# NanoRS485-MySens-v015.net
KiCad netlist of a schematic drawn in EAGLE
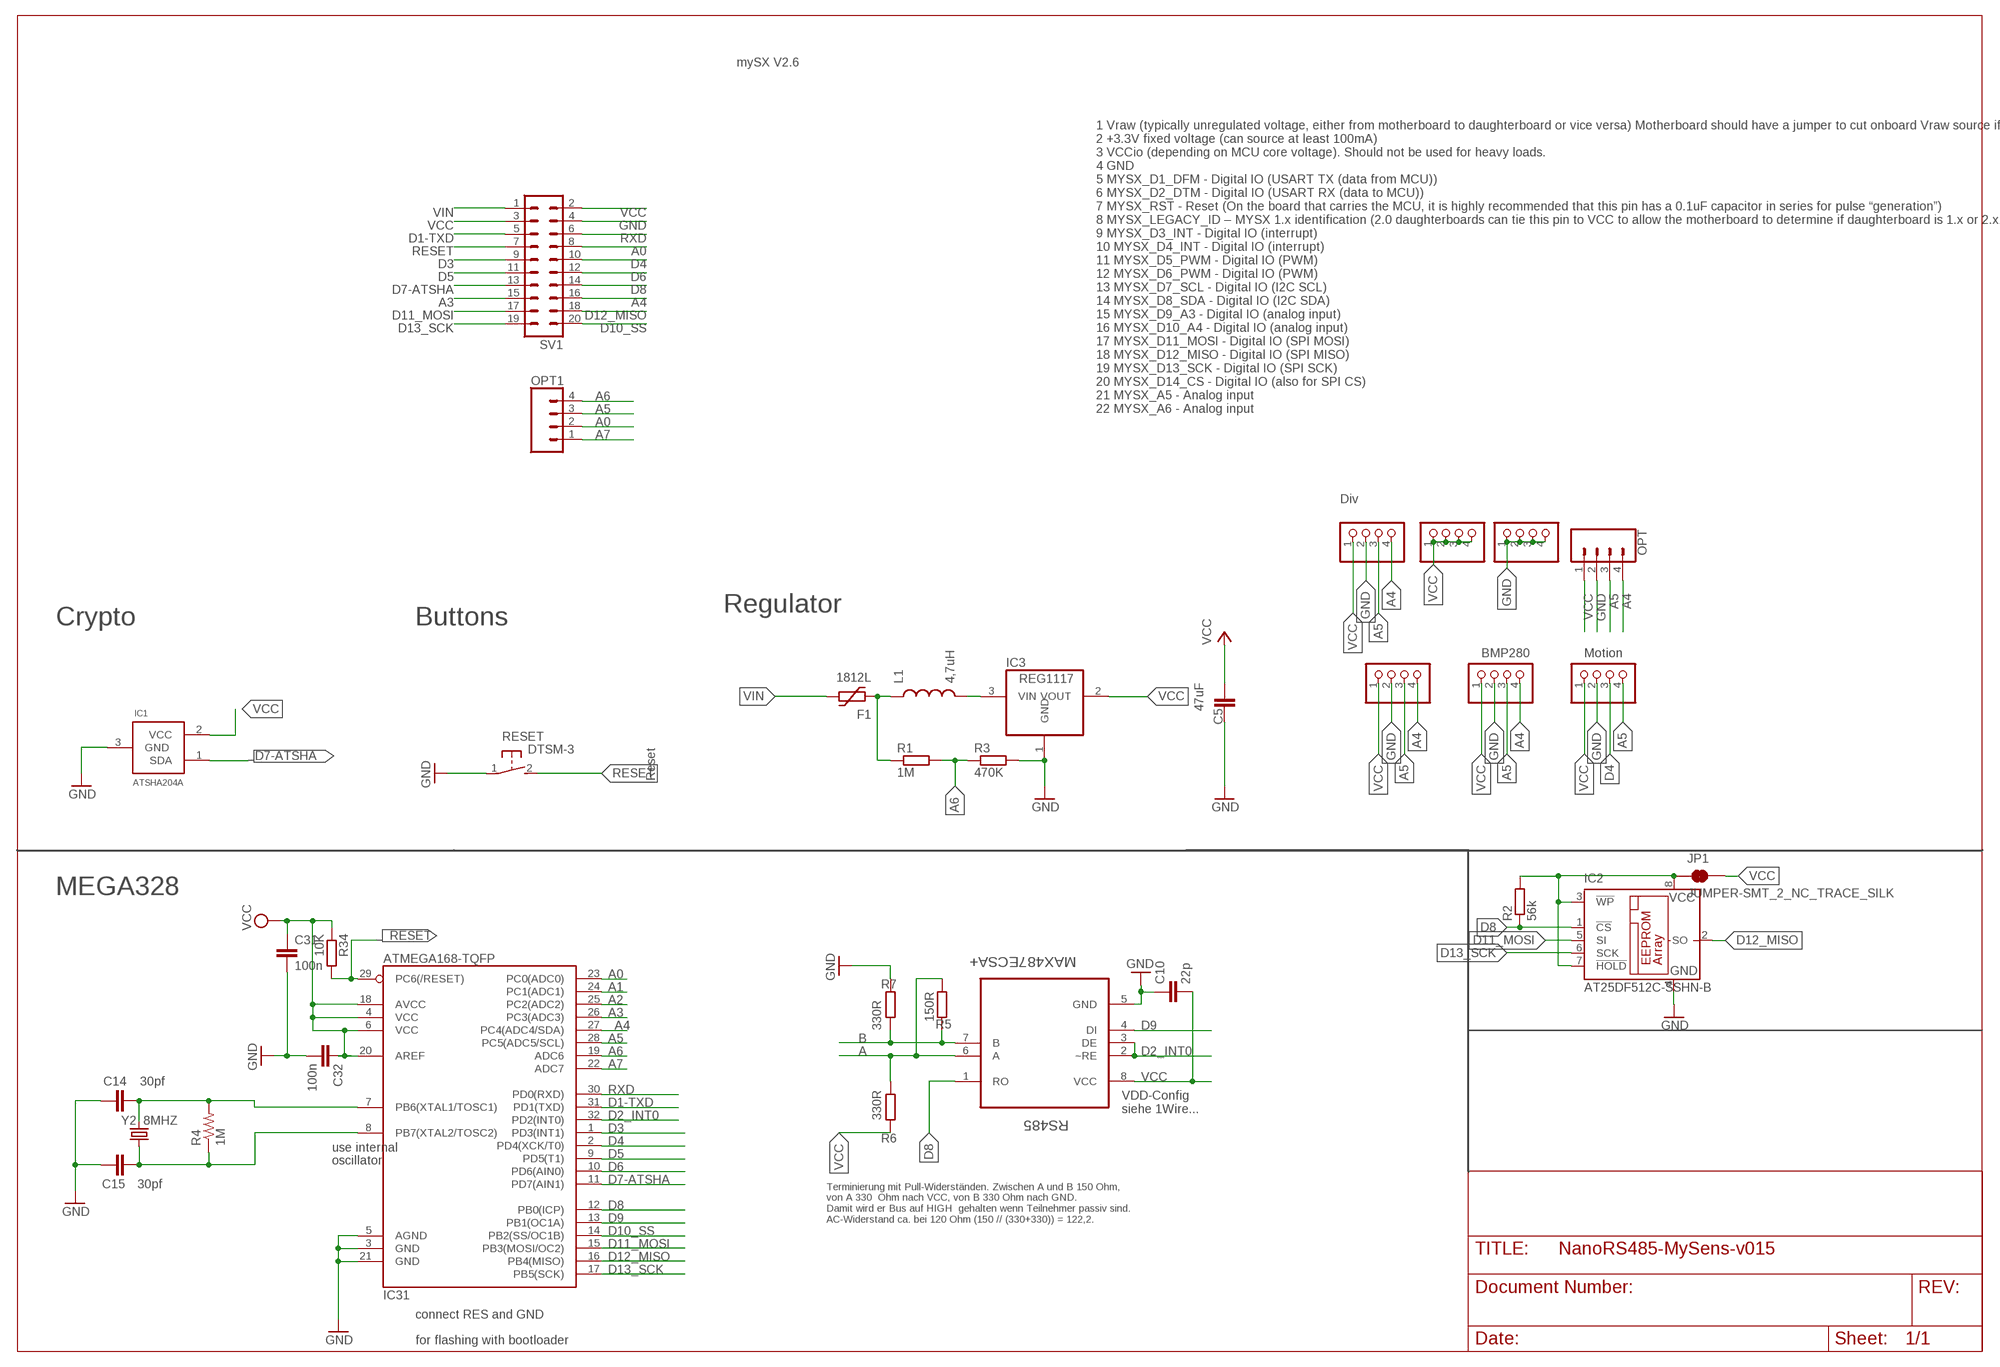
[diagram p0: schematic, sheet 1, part 1 of 2]
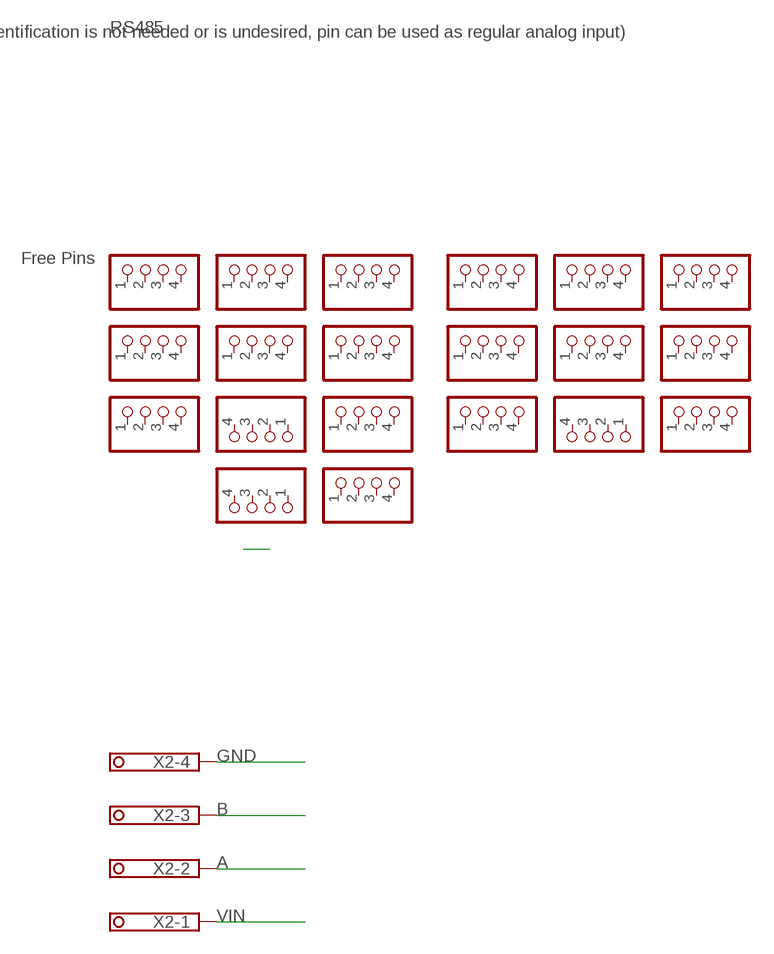
[diagram p1: schematic, sheet 1, part 2 of 2]

(export (version "E")
  (design (tool "Eeschema 10.0.6"))
  (components
    (comp (ref "BH1750")
      (value "PINHD-1X04_2.54-S")
      (footprint "eagle-import:1X04-S")
      (libsource (lib "eagle-import") (part "PINHD-1X04_2.54-S"))
    )
    (comp (ref "C5")
      (value "47uF")
      (footprint "eagle-import:C1210")
      (libsource (lib "eagle-import") (part "C-EUC1210"))
    )
    (comp (ref "C10")
      (value "22p")
      (footprint "eagle-import:C0805")
      (libsource (lib "eagle-import") (part "C-EUC0805"))
    )
    (comp (ref "C14")
      (value "30pf")
      (footprint "eagle-import:0805")
      (libsource (lib "eagle-import") (part "CAP0805"))
    )
    (comp (ref "C15")
      (value "30pf")
      (footprint "eagle-import:0805")
      (libsource (lib "eagle-import") (part "CAP0805"))
    )
    (comp (ref "C31")
      (value "100n")
      (footprint "eagle-import:C0805")
      (libsource (lib "eagle-import") (part "C-EUC0805"))
    )
    (comp (ref "C32")
      (value "100n")
      (footprint "eagle-import:C0805")
      (libsource (lib "eagle-import") (part "C-EUC0805"))
    )
    (comp (ref "F1")
      (value "1812L")
      (footprint "eagle-import:1812L")
      (libsource (lib "eagle-import") (part "1812L"))
    )
    (comp (ref "I2C-1")
      (value "PINHD-1X04_2.54-S")
      (footprint "eagle-import:1X04-S")
      (libsource (lib "eagle-import") (part "PINHD-1X04_2.54-S"))
    )
    (comp (ref "I2C-2")
      (value "PINHD-1X04_2.54-S")
      (footprint "eagle-import:1X04-S")
      (libsource (lib "eagle-import") (part "PINHD-1X04_2.54-S"))
    )
    (comp (ref "IC1")
      (value "ATSHA204A")
      (footprint "eagle-import:SOT23")
      (libsource (lib "eagle-import") (part "ATSHA204A"))
    )
    (comp (ref "IC2")
      (value "AT25DF512C-SSHN-B")
      (footprint "eagle-import:SO-08")
      (fields (field (name "MF") "MICROCHIP") (field (name "MPN") "25AA080/SN"))
      (libsource (lib "eagle-import") (part "25SNAA080"))
    )
    (comp (ref "IC3")
      (value "REG1117")
      (footprint "eagle-import:SOT223")
      (libsource (lib "eagle-import") (part "REG1117"))
    )
    (comp (ref "IC31")
      (value "ATMEGA168-TQFP")
      (footprint "eagle-import:TQFP32-08")
      (libsource (lib "eagle-import") (part "ATMEGA168-TQFP"))
    )
    (comp (ref "JP1")
      (value "JUMPER-SMT_2_NC_TRACE_SILK")
      (footprint "eagle-import:SMT-JUMPER_2_NC_TRACE_SILK")
      (libsource (lib "eagle-import") (part "JUMPER-SMT_2_NC_TRACE_SILK"))
    )
    (comp (ref "JP2")
      (value "PINHD-1X04_2.54-S")
      (footprint "eagle-import:1X04-S")
      (libsource (lib "eagle-import") (part "PINHD-1X04_2.54-S"))
    )
    (comp (ref "JP3")
      (value "PINHD-1X04_2.54-S")
      (footprint "eagle-import:1X04-S")
      (libsource (lib "eagle-import") (part "PINHD-1X04_2.54-S"))
    )
    (comp (ref "JP4")
      (value "PINHD-1X04_2.54-S")
      (footprint "eagle-import:1X04-S")
      (libsource (lib "eagle-import") (part "PINHD-1X04_2.54-S"))
    )
    (comp (ref "JP5")
      (value "PINHD-1X04_2.54-S")
      (footprint "eagle-import:1X04-S")
      (libsource (lib "eagle-import") (part "PINHD-1X04_2.54-S"))
    )
    (comp (ref "JP6")
      (value "PINHD-1X04_2.54-S")
      (footprint "eagle-import:1X04-S")
      (libsource (lib "eagle-import") (part "PINHD-1X04_2.54-S"))
    )
    (comp (ref "JP7")
      (value "PINHD-1X04_2.54-S")
      (footprint "eagle-import:1X04-S")
      (libsource (lib "eagle-import") (part "PINHD-1X04_2.54-S"))
    )
    (comp (ref "JP8")
      (value "PINHD-1X04_2.54-S")
      (footprint "eagle-import:1X04-S")
      (libsource (lib "eagle-import") (part "PINHD-1X04_2.54-S"))
    )
    (comp (ref "JP9")
      (value "PINHD-1X04_2.54-S")
      (footprint "eagle-import:1X04-S")
      (libsource (lib "eagle-import") (part "PINHD-1X04_2.54-S"))
    )
    (comp (ref "JP10")
      (value "PINHD-1X04_2.54-S")
      (footprint "eagle-import:1X04-S")
      (libsource (lib "eagle-import") (part "PINHD-1X04_2.54-S"))
    )
    (comp (ref "JP11")
      (value "PINHD-1X04_2.54-S")
      (footprint "eagle-import:1X04-S")
      (libsource (lib "eagle-import") (part "PINHD-1X04_2.54-S"))
    )
    (comp (ref "JP12")
      (value "PINHD-1X04_2.54-S")
      (footprint "eagle-import:1X04-S")
      (libsource (lib "eagle-import") (part "PINHD-1X04_2.54-S"))
    )
    (comp (ref "JP13")
      (value "PINHD-1X04_2.54-S")
      (footprint "eagle-import:1X04-S")
      (libsource (lib "eagle-import") (part "PINHD-1X04_2.54-S"))
    )
    (comp (ref "JP14")
      (value "PINHD-1X04_2.54-S")
      (footprint "eagle-import:1X04-S")
      (libsource (lib "eagle-import") (part "PINHD-1X04_2.54-S"))
    )
    (comp (ref "JP15")
      (value "PINHD-1X04_2.54-S")
      (footprint "eagle-import:1X04-S")
      (libsource (lib "eagle-import") (part "PINHD-1X04_2.54-S"))
    )
    (comp (ref "JP16")
      (value "PINHD-1X04_2.54-S")
      (footprint "eagle-import:1X04-S")
      (libsource (lib "eagle-import") (part "PINHD-1X04_2.54-S"))
    )
    (comp (ref "JP17")
      (value "PINHD-1X04_2.54-S")
      (footprint "eagle-import:1X04-S")
      (libsource (lib "eagle-import") (part "PINHD-1X04_2.54-S"))
    )
    (comp (ref "JP18")
      (value "PINHD-1X04_2.54-S")
      (footprint "eagle-import:1X04-S")
      (libsource (lib "eagle-import") (part "PINHD-1X04_2.54-S"))
    )
    (comp (ref "JP19")
      (value "PINHD-1X04_2.54-S")
      (footprint "eagle-import:1X04-S")
      (libsource (lib "eagle-import") (part "PINHD-1X04_2.54-S"))
    )
    (comp (ref "JP20")
      (value "PINHD-1X04_2.54-S")
      (footprint "eagle-import:1X04-S")
      (libsource (lib "eagle-import") (part "PINHD-1X04_2.54-S"))
    )
    (comp (ref "JP21")
      (value "PINHD-1X04_2.54-S")
      (footprint "eagle-import:1X04-S")
      (libsource (lib "eagle-import") (part "PINHD-1X04_2.54-S"))
    )
    (comp (ref "JP22")
      (value "PINHD-1X04_2.54-S")
      (footprint "eagle-import:1X04-S")
      (libsource (lib "eagle-import") (part "PINHD-1X04_2.54-S"))
    )
    (comp (ref "JP23")
      (value "PINHD-1X04_2.54-S")
      (footprint "eagle-import:1X04-S")
      (libsource (lib "eagle-import") (part "PINHD-1X04_2.54-S"))
    )
    (comp (ref "L1")
      (value "4,7uH")
      (footprint "eagle-import:0805")
      (libsource (lib "eagle-import") (part "INDUCTOR0805"))
    )
    (comp (ref "MOTION")
      (value "PINHD-1X04_2.54-S")
      (footprint "eagle-import:1X04-S")
      (libsource (lib "eagle-import") (part "PINHD-1X04_2.54-S"))
    )
    (comp (ref "OPT")
      (value "CONN_04")
      (footprint "eagle-import:1X04")
      (libsource (lib "eagle-import") (part "CONN_04"))
    )
    (comp (ref "OPT1")
      (value "CONN_04")
      (footprint "eagle-import:1X04")
      (libsource (lib "eagle-import") (part "CONN_04"))
    )
    (comp (ref "R1")
      (value "1M")
      (footprint "eagle-import:R0805")
      (libsource (lib "eagle-import") (part "R-EU_R0805"))
    )
    (comp (ref "R2")
      (value "56k")
      (footprint "eagle-import:M0805")
      (libsource (lib "eagle-import") (part "resistor_R-EU_M0805"))
    )
    (comp (ref "R3")
      (value "470K")
      (footprint "eagle-import:R0805")
      (libsource (lib "eagle-import") (part "R-EU_R0805"))
    )
    (comp (ref "R4")
      (value "1M")
      (footprint "eagle-import:0805")
      (libsource (lib "eagle-import") (part "RESISTOR0805-RES"))
    )
    (comp (ref "R5")
      (value "150R")
      (footprint "eagle-import:R0805")
      (libsource (lib "eagle-import") (part "R-EU_R0805"))
    )
    (comp (ref "R6")
      (value "330R")
      (footprint "eagle-import:R0805")
      (libsource (lib "eagle-import") (part "R-EU_R0805"))
    )
    (comp (ref "R7")
      (value "330R")
      (footprint "eagle-import:R0805")
      (libsource (lib "eagle-import") (part "R-EU_R0805"))
    )
    (comp (ref "R34")
      (value "10K")
      (footprint "eagle-import:R0805")
      (libsource (lib "eagle-import") (part "R-EU_R0805"))
    )
    (comp (ref "RESET")
      (value "DTSM-3")
      (footprint "eagle-import:DTSM-3")
      (libsource (lib "eagle-import") (part "DTSM-3"))
    )
    (comp (ref "RS485")
      (value "MAX487ECSA+")
      (footprint "eagle-import:SOIC127P600X175-8N")
      (libsource (lib "eagle-import") (part "MAX487ECSA+"))
    )
    (comp (ref "SV1")
      (value "MA10-2")
      (footprint "eagle-import:MA10-2")
      (libsource (lib "eagle-import") (part "MA10-2"))
    )
    (comp (ref "X2")
      (value "1751264")
      (footprint "eagle-import:1751264")
      (libsource (lib "eagle-import") (part "1751264"))
    )
    (comp (ref "Y2")
      (value "8MHZ")
      (footprint "eagle-import:CRYSTAL-TXC-7A")
      (libsource (lib "eagle-import") (part "CRYSTALTXC-7A"))
    )
  )
  (nets
    (net (code "1") (name "/A") (class "Default")
      (node (ref "R5") (pin "1") (pinfunction "1_1") (pintype "passive"))
      (node (ref "R6") (pin "2") (pinfunction "2_2") (pintype "passive"))
      (node (ref "RS485") (pin "6") (pinfunction "A_6") (pintype "bidirectional"))
      (node (ref "X2") (pin "2") (pinfunction "K_2") (pintype "passive"))
    )
    (net (code "2") (name "/A0") (class "Default")
      (node (ref "IC31") (pin "23") (pinfunction "PC0(ADC0)_23") (pintype "bidirectional"))
      (node (ref "OPT1") (pin "2") (pinfunction "2_2") (pintype "passive"))
      (node (ref "SV1") (pin "8") (pinfunction "8_8") (pintype "passive"))
    )
    (net (code "3") (name "/A1") (class "Default")
      (node (ref "IC31") (pin "24") (pinfunction "PC1(ADC1)_24") (pintype "bidirectional"))
    )
    (net (code "4") (name "/A2") (class "Default")
      (node (ref "IC31") (pin "25") (pinfunction "PC2(ADC2)_25") (pintype "bidirectional"))
    )
    (net (code "5") (name "/A3") (class "Default")
      (node (ref "IC31") (pin "26") (pinfunction "PC3(ADC3)_26") (pintype "bidirectional"))
      (node (ref "SV1") (pin "15") (pinfunction "15_15") (pintype "passive"))
    )
    (net (code "6") (name "/A7") (class "Default")
      (node (ref "IC31") (pin "22") (pinfunction "ADC7_22") (pintype "bidirectional"))
      (node (ref "OPT1") (pin "1") (pinfunction "1_1") (pintype "passive"))
    )
    (net (code "7") (name "/B") (class "Default")
      (node (ref "R5") (pin "2") (pinfunction "2_2") (pintype "passive"))
      (node (ref "R7") (pin "1") (pinfunction "1_1") (pintype "passive"))
      (node (ref "RS485") (pin "7") (pinfunction "B_7") (pintype "bidirectional"))
      (node (ref "X2") (pin "3") (pinfunction "K_3") (pintype "passive"))
    )
    (net (code "8") (name "/D1-TXD") (class "Default")
      (node (ref "IC31") (pin "31") (pinfunction "PD1(TXD)_31") (pintype "bidirectional"))
      (node (ref "SV1") (pin "5") (pinfunction "5_5") (pintype "passive"))
    )
    (net (code "9") (name "/D2_INT0") (class "Default")
      (node (ref "IC31") (pin "32") (pinfunction "PD2(INT0)_32") (pintype "bidirectional"))
      (node (ref "RS485") (pin "2") (pinfunction "~{RE}_2") (pintype "input"))
      (node (ref "RS485") (pin "3") (pinfunction "DE_3") (pintype "input"))
    )
    (net (code "10") (name "/D3") (class "Default")
      (node (ref "IC31") (pin "1") (pinfunction "PD3(INT1)_1") (pintype "bidirectional"))
      (node (ref "SV1") (pin "9") (pinfunction "9_9") (pintype "passive"))
    )
    (net (code "11") (name "/D5") (class "Default")
      (node (ref "IC31") (pin "9") (pinfunction "PD5(T1)_9") (pintype "bidirectional"))
      (node (ref "SV1") (pin "11") (pinfunction "11_11") (pintype "passive"))
    )
    (net (code "12") (name "/D6") (class "Default")
      (node (ref "IC31") (pin "10") (pinfunction "PD6(AIN0)_10") (pintype "bidirectional"))
      (node (ref "SV1") (pin "12") (pinfunction "12_12") (pintype "passive"))
    )
    (net (code "13") (name "/D7-ATSHA") (class "Default")
      (node (ref "IC1") (pin "1") (pinfunction "SDA_1") (pintype "bidirectional"))
      (node (ref "IC31") (pin "11") (pinfunction "PD7(AIN1)_11") (pintype "bidirectional"))
      (node (ref "SV1") (pin "13") (pinfunction "13_13") (pintype "passive"))
    )
    (net (code "14") (name "/D9") (class "Default")
      (node (ref "IC31") (pin "13") (pinfunction "PB1(OC1A)_13") (pintype "bidirectional"))
      (node (ref "RS485") (pin "4") (pinfunction "DI_4") (pintype "input"))
    )
    (net (code "15") (name "/D10_SS") (class "Default")
      (node (ref "IC31") (pin "14") (pinfunction "PB2(SS/OC1B)_14") (pintype "bidirectional"))
      (node (ref "SV1") (pin "20") (pinfunction "20_20") (pintype "passive"))
    )
    (net (code "16") (name "/RXD") (class "Default")
      (node (ref "IC31") (pin "30") (pinfunction "PD0(RXD)_30") (pintype "bidirectional"))
      (node (ref "SV1") (pin "6") (pinfunction "6_6") (pintype "passive"))
    )
    (net (code "17") (name "A4") (class "Default")
      (node (ref "BH1750") (pin "4") (pinfunction "4_4") (pintype "passive"))
      (node (ref "I2C-1") (pin "4") (pinfunction "4_4") (pintype "passive"))
      (node (ref "I2C-2") (pin "4") (pinfunction "4_4") (pintype "passive"))
      (node (ref "IC31") (pin "27") (pinfunction "PC4(ADC4/SDA)_27") (pintype "bidirectional"))
      (node (ref "OPT") (pin "4") (pinfunction "4_4") (pintype "passive"))
      (node (ref "SV1") (pin "16") (pinfunction "16_16") (pintype "passive"))
    )
    (net (code "18") (name "A5") (class "Default")
      (node (ref "BH1750") (pin "3") (pinfunction "3_3") (pintype "passive"))
      (node (ref "I2C-1") (pin "3") (pinfunction "3_3") (pintype "passive"))
      (node (ref "I2C-2") (pin "3") (pinfunction "3_3") (pintype "passive"))
      (node (ref "IC31") (pin "28") (pinfunction "PC5(ADC5/SCL)_28") (pintype "bidirectional"))
      (node (ref "MOTION") (pin "4") (pinfunction "4_4") (pintype "passive"))
      (node (ref "OPT") (pin "3") (pinfunction "3_3") (pintype "passive"))
      (node (ref "OPT1") (pin "3") (pinfunction "3_3") (pintype "passive"))
    )
    (net (code "19") (name "A6") (class "Default")
      (node (ref "IC31") (pin "19") (pinfunction "ADC6_19") (pintype "bidirectional"))
      (node (ref "OPT1") (pin "4") (pinfunction "4_4") (pintype "passive"))
      (node (ref "R1") (pin "2") (pinfunction "2_2") (pintype "passive"))
      (node (ref "R3") (pin "1") (pinfunction "1_1") (pintype "passive"))
    )
    (net (code "20") (name "D4") (class "Default")
      (node (ref "IC31") (pin "2") (pinfunction "PD4(XCK/T0)_2") (pintype "bidirectional"))
      (node (ref "MOTION") (pin "3") (pinfunction "3_3") (pintype "passive"))
      (node (ref "SV1") (pin "10") (pinfunction "10_10") (pintype "passive"))
    )
    (net (code "21") (name "D8") (class "Default")
      (node (ref "IC2") (pin "1") (pinfunction "~{CS}_1") (pintype "input"))
      (node (ref "IC31") (pin "12") (pinfunction "PB0(ICP)_12") (pintype "bidirectional"))
      (node (ref "R2") (pin "1") (pinfunction "1_1") (pintype "passive"))
      (node (ref "RS485") (pin "1") (pinfunction "RO_1") (pintype "output"))
      (node (ref "SV1") (pin "14") (pinfunction "14_14") (pintype "passive"))
    )
    (net (code "22") (name "D11_MOSI") (class "Default")
      (node (ref "IC2") (pin "5") (pinfunction "SI_5") (pintype "input"))
      (node (ref "IC31") (pin "15") (pinfunction "PB3(MOSI/OC2)_15") (pintype "bidirectional"))
      (node (ref "SV1") (pin "17") (pinfunction "17_17") (pintype "passive"))
    )
    (net (code "23") (name "D12_MISO") (class "Default")
      (node (ref "IC2") (pin "2") (pinfunction "SO_2") (pintype "bidirectional"))
      (node (ref "IC31") (pin "16") (pinfunction "PB4(MISO)_16") (pintype "bidirectional"))
      (node (ref "SV1") (pin "18") (pinfunction "18_18") (pintype "passive"))
    )
    (net (code "24") (name "D13_SCK") (class "Default")
      (node (ref "IC2") (pin "6") (pinfunction "SCK_6") (pintype "input"))
      (node (ref "IC31") (pin "17") (pinfunction "PB5(SCK)_17") (pintype "bidirectional"))
      (node (ref "SV1") (pin "19") (pinfunction "19_19") (pintype "passive"))
    )
    (net (code "25") (name "GND") (class "Default")
      (node (ref "BH1750") (pin "2") (pinfunction "2_2") (pintype "passive"))
      (node (ref "C10") (pin "1") (pinfunction "1_1") (pintype "passive"))
      (node (ref "C14") (pin "1") (pinfunction "1_1") (pintype "passive"))
      (node (ref "C15") (pin "1") (pinfunction "1_1") (pintype "passive"))
      (node (ref "C31") (pin "2") (pinfunction "2_2") (pintype "passive"))
      (node (ref "C32") (pin "2") (pinfunction "2_2") (pintype "passive"))
      (node (ref "C5") (pin "1") (pinfunction "1_1") (pintype "passive"))
      (node (ref "I2C-1") (pin "2") (pinfunction "2_2") (pintype "passive"))
      (node (ref "I2C-2") (pin "2") (pinfunction "2_2") (pintype "passive"))
      (node (ref "IC1") (pin "3") (pinfunction "GND_3") (pintype "bidirectional"))
      (node (ref "IC2") (pin "4") (pinfunction "GND_4") (pintype "power_in"))
      (node (ref "IC3") (pin "1") (pinfunction "GND_1") (pintype "power_in"))
      (node (ref "IC31") (pin "21") (pinfunction "GND_21") (pintype "bidirectional"))
      (node (ref "IC31") (pin "3") (pinfunction "GND_3") (pintype "bidirectional"))
      (node (ref "IC31") (pin "5") (pinfunction "AGND_5") (pintype "bidirectional"))
      (node (ref "JP2") (pin "1") (pinfunction "1_1") (pintype "passive"))
      (node (ref "JP2") (pin "2") (pinfunction "2_2") (pintype "passive"))
      (node (ref "JP2") (pin "3") (pinfunction "3_3") (pintype "passive"))
      (node (ref "JP2") (pin "4") (pinfunction "4_4") (pintype "passive"))
      (node (ref "MOTION") (pin "2") (pinfunction "2_2") (pintype "passive"))
      (node (ref "OPT") (pin "2") (pinfunction "2_2") (pintype "passive"))
      (node (ref "R3") (pin "2") (pinfunction "2_2") (pintype "passive"))
      (node (ref "R7") (pin "2") (pinfunction "2_2") (pintype "passive"))
      (node (ref "RESET") (pin "1") (pinfunction "1_1") (pintype "passive"))
      (node (ref "RS485") (pin "5") (pinfunction "GND_5") (pintype "passive"))
      (node (ref "SV1") (pin "4") (pinfunction "4_4") (pintype "passive"))
      (node (ref "X2") (pin "4") (pinfunction "K_4") (pintype "passive"))
    )
    (net (code "26") (name "Net-(F1-1)") (class "Default")
      (node (ref "F1") (pin "P$1") (pinfunction "1_P$1") (pintype "passive"))
      (node (ref "L1") (pin "1") (pinfunction "1_1") (pintype "passive"))
      (node (ref "R1") (pin "1") (pinfunction "1_1") (pintype "passive"))
    )
    (net (code "27") (name "Net-(IC2-VCC)") (class "Default")
      (node (ref "IC2") (pin "3") (pinfunction "~{WP}_3") (pintype "input"))
      (node (ref "IC2") (pin "7") (pinfunction "~{HOLD}_7") (pintype "input"))
      (node (ref "IC2") (pin "8") (pinfunction "VCC_8") (pintype "power_in"))
      (node (ref "JP1") (pin "1") (pinfunction "1_1") (pintype "passive"))
      (node (ref "R2") (pin "2") (pinfunction "2_2") (pintype "passive"))
    )
    (net (code "28") (name "Net-(IC3-VIN)") (class "Default")
      (node (ref "IC3") (pin "3") (pinfunction "VIN_3") (pintype "input"))
      (node (ref "L1") (pin "2") (pinfunction "2_2") (pintype "passive"))
    )
    (net (code "29") (name "Net-(IC31-PB6(XTAL1{slash}TOSC1))") (class "Default")
      (node (ref "C14") (pin "2") (pinfunction "2_2") (pintype "passive"))
      (node (ref "IC31") (pin "7") (pinfunction "PB6(XTAL1/TOSC1)_7") (pintype "bidirectional"))
      (node (ref "R4") (pin "2") (pinfunction "2_2") (pintype "passive"))
      (node (ref "Y2") (pin "P$2") (pinfunction "2_P$2") (pintype "passive"))
    )
    (net (code "30") (name "Net-(IC31-PB7(XTAL2{slash}TOSC2))") (class "Default")
      (node (ref "C15") (pin "2") (pinfunction "2_2") (pintype "passive"))
      (node (ref "IC31") (pin "8") (pinfunction "PB7(XTAL2/TOSC2)_8") (pintype "bidirectional"))
      (node (ref "R4") (pin "1") (pinfunction "1_1") (pintype "passive"))
      (node (ref "Y2") (pin "P$1") (pinfunction "1_P$1") (pintype "passive"))
    )
    (net (code "31") (name "RESET") (class "Default")
      (node (ref "IC31") (pin "29") (pinfunction "PC6(/RESET)_29") (pintype "bidirectional"))
      (node (ref "R34") (pin "2") (pinfunction "2_2") (pintype "passive"))
      (node (ref "RESET") (pin "2") (pinfunction "2_2") (pintype "passive"))
      (node (ref "SV1") (pin "7") (pinfunction "7_7") (pintype "passive"))
    )
    (net (code "32") (name "VCC") (class "Default")
      (node (ref "BH1750") (pin "1") (pinfunction "1_1") (pintype "passive"))
      (node (ref "C10") (pin "2") (pinfunction "2_2") (pintype "passive"))
      (node (ref "C31") (pin "1") (pinfunction "1_1") (pintype "passive"))
      (node (ref "C32") (pin "1") (pinfunction "1_1") (pintype "passive"))
      (node (ref "C5") (pin "2") (pinfunction "2_2") (pintype "passive"))
      (node (ref "I2C-1") (pin "1") (pinfunction "1_1") (pintype "passive"))
      (node (ref "I2C-2") (pin "1") (pinfunction "1_1") (pintype "passive"))
      (node (ref "IC1") (pin "2") (pinfunction "VCC_2") (pintype "bidirectional"))
      (node (ref "IC3") (pin "2") (pinfunction "VOUT_2") (pintype "output"))
      (node (ref "IC31") (pin "18") (pinfunction "AVCC_18") (pintype "bidirectional"))
      (node (ref "IC31") (pin "20") (pinfunction "AREF_20") (pintype "bidirectional"))
      (node (ref "IC31") (pin "4") (pinfunction "VCC_4") (pintype "bidirectional"))
      (node (ref "IC31") (pin "6") (pinfunction "VCC_6") (pintype "bidirectional"))
      (node (ref "JP1") (pin "2") (pinfunction "2_2") (pintype "passive"))
      (node (ref "JP3") (pin "1") (pinfunction "1_1") (pintype "passive"))
      (node (ref "JP3") (pin "2") (pinfunction "2_2") (pintype "passive"))
      (node (ref "JP3") (pin "3") (pinfunction "3_3") (pintype "passive"))
      (node (ref "JP3") (pin "4") (pinfunction "4_4") (pintype "passive"))
      (node (ref "MOTION") (pin "1") (pinfunction "1_1") (pintype "passive"))
      (node (ref "OPT") (pin "1") (pinfunction "1_1") (pintype "passive"))
      (node (ref "R34") (pin "1") (pinfunction "1_1") (pintype "passive"))
      (node (ref "R6") (pin "1") (pinfunction "1_1") (pintype "passive"))
      (node (ref "RS485") (pin "8") (pinfunction "VCC_8") (pintype "power_in"))
      (node (ref "SV1") (pin "2") (pinfunction "2_2") (pintype "passive"))
      (node (ref "SV1") (pin "3") (pinfunction "3_3") (pintype "passive"))
    )
    (net (code "33") (name "VIN") (class "Default")
      (node (ref "F1") (pin "P$2") (pinfunction "2_P$2") (pintype "passive"))
      (node (ref "SV1") (pin "1") (pinfunction "1_1") (pintype "passive"))
      (node (ref "X2") (pin "1") (pinfunction "K_1") (pintype "passive"))
    )
    (net (code "34") (name "unconnected-(JP4-Pad1)") (class "Default")
      (node (ref "JP4") (pin "1") (pinfunction "1_1") (pintype "passive"))
    )
    (net (code "35") (name "unconnected-(JP4-Pad2)") (class "Default")
      (node (ref "JP4") (pin "2") (pinfunction "2_2") (pintype "passive"))
    )
    (net (code "36") (name "unconnected-(JP4-Pad3)") (class "Default")
      (node (ref "JP4") (pin "3") (pinfunction "3_3") (pintype "passive"))
    )
    (net (code "37") (name "unconnected-(JP4-Pad4)") (class "Default")
      (node (ref "JP4") (pin "4") (pinfunction "4_4") (pintype "passive"))
    )
    (net (code "38") (name "unconnected-(JP5-Pad1)") (class "Default")
      (node (ref "JP5") (pin "1") (pinfunction "1_1") (pintype "passive"))
    )
    (net (code "39") (name "unconnected-(JP5-Pad2)") (class "Default")
      (node (ref "JP5") (pin "2") (pinfunction "2_2") (pintype "passive"))
    )
    (net (code "40") (name "unconnected-(JP5-Pad3)") (class "Default")
      (node (ref "JP5") (pin "3") (pinfunction "3_3") (pintype "passive"))
    )
    (net (code "41") (name "unconnected-(JP5-Pad4)") (class "Default")
      (node (ref "JP5") (pin "4") (pinfunction "4_4") (pintype "passive"))
    )
    (net (code "42") (name "unconnected-(JP6-Pad1)") (class "Default")
      (node (ref "JP6") (pin "1") (pinfunction "1_1") (pintype "passive"))
    )
    (net (code "43") (name "unconnected-(JP6-Pad2)") (class "Default")
      (node (ref "JP6") (pin "2") (pinfunction "2_2") (pintype "passive"))
    )
    (net (code "44") (name "unconnected-(JP6-Pad3)") (class "Default")
      (node (ref "JP6") (pin "3") (pinfunction "3_3") (pintype "passive"))
    )
    (net (code "45") (name "unconnected-(JP6-Pad4)") (class "Default")
      (node (ref "JP6") (pin "4") (pinfunction "4_4") (pintype "passive"))
    )
    (net (code "46") (name "unconnected-(JP7-Pad1)") (class "Default")
      (node (ref "JP7") (pin "1") (pinfunction "1_1") (pintype "passive"))
    )
    (net (code "47") (name "unconnected-(JP7-Pad2)") (class "Default")
      (node (ref "JP7") (pin "2") (pinfunction "2_2") (pintype "passive"))
    )
    (net (code "48") (name "unconnected-(JP7-Pad3)") (class "Default")
      (node (ref "JP7") (pin "3") (pinfunction "3_3") (pintype "passive"))
    )
    (net (code "49") (name "unconnected-(JP7-Pad4)") (class "Default")
      (node (ref "JP7") (pin "4") (pinfunction "4_4") (pintype "passive"))
    )
    (net (code "50") (name "unconnected-(JP8-Pad1)") (class "Default")
      (node (ref "JP8") (pin "1") (pinfunction "1_1") (pintype "passive"))
    )
    (net (code "51") (name "unconnected-(JP8-Pad2)") (class "Default")
      (node (ref "JP8") (pin "2") (pinfunction "2_2") (pintype "passive"))
    )
    (net (code "52") (name "unconnected-(JP8-Pad3)") (class "Default")
      (node (ref "JP8") (pin "3") (pinfunction "3_3") (pintype "passive"))
    )
    (net (code "53") (name "unconnected-(JP8-Pad4)") (class "Default")
      (node (ref "JP8") (pin "4") (pinfunction "4_4") (pintype "passive"))
    )
    (net (code "54") (name "unconnected-(JP9-Pad1)") (class "Default")
      (node (ref "JP9") (pin "1") (pinfunction "1_1") (pintype "passive"))
    )
    (net (code "55") (name "unconnected-(JP9-Pad2)") (class "Default")
      (node (ref "JP9") (pin "2") (pinfunction "2_2") (pintype "passive"))
    )
    (net (code "56") (name "unconnected-(JP9-Pad3)") (class "Default")
      (node (ref "JP9") (pin "3") (pinfunction "3_3") (pintype "passive"))
    )
    (net (code "57") (name "unconnected-(JP9-Pad4)") (class "Default")
      (node (ref "JP9") (pin "4") (pinfunction "4_4") (pintype "passive"))
    )
    (net (code "58") (name "unconnected-(JP10-Pad1)") (class "Default")
      (node (ref "JP10") (pin "1") (pinfunction "1_1") (pintype "passive"))
    )
    (net (code "59") (name "unconnected-(JP10-Pad2)") (class "Default")
      (node (ref "JP10") (pin "2") (pinfunction "2_2") (pintype "passive"))
    )
    (net (code "60") (name "unconnected-(JP10-Pad3)") (class "Default")
      (node (ref "JP10") (pin "3") (pinfunction "3_3") (pintype "passive"))
    )
    (net (code "61") (name "unconnected-(JP10-Pad4)") (class "Default")
      (node (ref "JP10") (pin "4") (pinfunction "4_4") (pintype "passive"))
    )
    (net (code "62") (name "unconnected-(JP11-Pad1)") (class "Default")
      (node (ref "JP11") (pin "1") (pinfunction "1_1") (pintype "passive"))
    )
    (net (code "63") (name "unconnected-(JP11-Pad2)") (class "Default")
      (node (ref "JP11") (pin "2") (pinfunction "2_2") (pintype "passive"))
    )
    (net (code "64") (name "unconnected-(JP11-Pad3)") (class "Default")
      (node (ref "JP11") (pin "3") (pinfunction "3_3") (pintype "passive"))
    )
    (net (code "65") (name "unconnected-(JP11-Pad4)") (class "Default")
      (node (ref "JP11") (pin "4") (pinfunction "4_4") (pintype "passive"))
    )
    (net (code "66") (name "unconnected-(JP12-Pad1)") (class "Default")
      (node (ref "JP12") (pin "1") (pinfunction "1_1") (pintype "passive"))
    )
    (net (code "67") (name "unconnected-(JP12-Pad2)") (class "Default")
      (node (ref "JP12") (pin "2") (pinfunction "2_2") (pintype "passive"))
    )
    (net (code "68") (name "unconnected-(JP12-Pad3)") (class "Default")
      (node (ref "JP12") (pin "3") (pinfunction "3_3") (pintype "passive"))
    )
    (net (code "69") (name "unconnected-(JP12-Pad4)") (class "Default")
      (node (ref "JP12") (pin "4") (pinfunction "4_4") (pintype "passive"))
    )
    (net (code "70") (name "unconnected-(JP13-Pad1)") (class "Default")
      (node (ref "JP13") (pin "1") (pinfunction "1_1") (pintype "passive"))
    )
    (net (code "71") (name "unconnected-(JP13-Pad2)") (class "Default")
      (node (ref "JP13") (pin "2") (pinfunction "2_2") (pintype "passive"))
    )
    (net (code "72") (name "unconnected-(JP13-Pad3)") (class "Default")
      (node (ref "JP13") (pin "3") (pinfunction "3_3") (pintype "passive"))
    )
    (net (code "73") (name "unconnected-(JP13-Pad4)") (class "Default")
      (node (ref "JP13") (pin "4") (pinfunction "4_4") (pintype "passive"))
    )
    (net (code "74") (name "unconnected-(JP14-Pad1)") (class "Default")
      (node (ref "JP14") (pin "1") (pinfunction "1_1") (pintype "passive"))
    )
    (net (code "75") (name "unconnected-(JP14-Pad2)") (class "Default")
      (node (ref "JP14") (pin "2") (pinfunction "2_2") (pintype "passive"))
    )
    (net (code "76") (name "unconnected-(JP14-Pad3)") (class "Default")
      (node (ref "JP14") (pin "3") (pinfunction "3_3") (pintype "passive"))
    )
    (net (code "77") (name "unconnected-(JP14-Pad4)") (class "Default")
      (node (ref "JP14") (pin "4") (pinfunction "4_4") (pintype "passive"))
    )
    (net (code "78") (name "unconnected-(JP15-Pad1)") (class "Default")
      (node (ref "JP15") (pin "1") (pinfunction "1_1") (pintype "passive"))
    )
    (net (code "79") (name "unconnected-(JP15-Pad2)") (class "Default")
      (node (ref "JP15") (pin "2") (pinfunction "2_2") (pintype "passive"))
    )
    (net (code "80") (name "unconnected-(JP15-Pad3)") (class "Default")
      (node (ref "JP15") (pin "3") (pinfunction "3_3") (pintype "passive"))
    )
    (net (code "81") (name "unconnected-(JP15-Pad4)") (class "Default")
      (node (ref "JP15") (pin "4") (pinfunction "4_4") (pintype "passive"))
    )
    (net (code "82") (name "unconnected-(JP16-Pad1)") (class "Default")
      (node (ref "JP16") (pin "1") (pinfunction "1_1") (pintype "passive"))
    )
    (net (code "83") (name "unconnected-(JP16-Pad2)") (class "Default")
      (node (ref "JP16") (pin "2") (pinfunction "2_2") (pintype "passive"))
    )
    (net (code "84") (name "unconnected-(JP16-Pad3)") (class "Default")
      (node (ref "JP16") (pin "3") (pinfunction "3_3") (pintype "passive"))
    )
    (net (code "85") (name "unconnected-(JP16-Pad4)") (class "Default")
      (node (ref "JP16") (pin "4") (pinfunction "4_4") (pintype "passive"))
    )
    (net (code "86") (name "unconnected-(JP17-Pad1)") (class "Default")
      (node (ref "JP17") (pin "1") (pinfunction "1_1") (pintype "passive"))
    )
    (net (code "87") (name "unconnected-(JP17-Pad2)") (class "Default")
      (node (ref "JP17") (pin "2") (pinfunction "2_2") (pintype "passive"))
    )
    (net (code "88") (name "unconnected-(JP17-Pad3)") (class "Default")
      (node (ref "JP17") (pin "3") (pinfunction "3_3") (pintype "passive"))
    )
    (net (code "89") (name "unconnected-(JP17-Pad4)") (class "Default")
      (node (ref "JP17") (pin "4") (pinfunction "4_4") (pintype "passive"))
    )
    (net (code "90") (name "unconnected-(JP18-Pad1)") (class "Default")
      (node (ref "JP18") (pin "1") (pinfunction "1_1") (pintype "passive"))
    )
    (net (code "91") (name "unconnected-(JP18-Pad2)") (class "Default")
      (node (ref "JP18") (pin "2") (pinfunction "2_2") (pintype "passive"))
    )
    (net (code "92") (name "unconnected-(JP18-Pad3)") (class "Default")
      (node (ref "JP18") (pin "3") (pinfunction "3_3") (pintype "passive"))
    )
    (net (code "93") (name "unconnected-(JP18-Pad4)") (class "Default")
      (node (ref "JP18") (pin "4") (pinfunction "4_4") (pintype "passive"))
    )
    (net (code "94") (name "unconnected-(JP19-Pad1)") (class "Default")
      (node (ref "JP19") (pin "1") (pinfunction "1_1") (pintype "passive"))
    )
    (net (code "95") (name "unconnected-(JP19-Pad2)") (class "Default")
      (node (ref "JP19") (pin "2") (pinfunction "2_2") (pintype "passive"))
    )
    (net (code "96") (name "unconnected-(JP19-Pad3)") (class "Default")
      (node (ref "JP19") (pin "3") (pinfunction "3_3") (pintype "passive"))
    )
    (net (code "97") (name "unconnected-(JP19-Pad4)") (class "Default")
      (node (ref "JP19") (pin "4") (pinfunction "4_4") (pintype "passive"))
    )
    (net (code "98") (name "unconnected-(JP20-Pad1)") (class "Default")
      (node (ref "JP20") (pin "1") (pinfunction "1_1") (pintype "passive"))
    )
    (net (code "99") (name "unconnected-(JP20-Pad2)") (class "Default")
      (node (ref "JP20") (pin "2") (pinfunction "2_2") (pintype "passive"))
    )
    (net (code "100") (name "unconnected-(JP20-Pad3)") (class "Default")
      (node (ref "JP20") (pin "3") (pinfunction "3_3") (pintype "passive"))
    )
    (net (code "101") (name "unconnected-(JP20-Pad4)") (class "Default")
      (node (ref "JP20") (pin "4") (pinfunction "4_4") (pintype "passive"))
    )
    (net (code "102") (name "unconnected-(JP21-Pad1)") (class "Default")
      (node (ref "JP21") (pin "1") (pinfunction "1_1") (pintype "passive"))
    )
    (net (code "103") (name "unconnected-(JP21-Pad2)") (class "Default")
      (node (ref "JP21") (pin "2") (pinfunction "2_2") (pintype "passive"))
    )
    (net (code "104") (name "unconnected-(JP21-Pad3)") (class "Default")
      (node (ref "JP21") (pin "3") (pinfunction "3_3") (pintype "passive"))
    )
    (net (code "105") (name "unconnected-(JP21-Pad4)") (class "Default")
      (node (ref "JP21") (pin "4") (pinfunction "4_4") (pintype "passive"))
    )
    (net (code "106") (name "unconnected-(JP22-Pad1)") (class "Default")
      (node (ref "JP22") (pin "1") (pinfunction "1_1") (pintype "passive"))
    )
    (net (code "107") (name "unconnected-(JP22-Pad2)") (class "Default")
      (node (ref "JP22") (pin "2") (pinfunction "2_2") (pintype "passive"))
    )
    (net (code "108") (name "unconnected-(JP22-Pad3)") (class "Default")
      (node (ref "JP22") (pin "3") (pinfunction "3_3") (pintype "passive"))
    )
    (net (code "109") (name "unconnected-(JP22-Pad4)") (class "Default")
      (node (ref "JP22") (pin "4") (pinfunction "4_4") (pintype "passive"))
    )
    (net (code "110") (name "unconnected-(JP23-Pad1)") (class "Default")
      (node (ref "JP23") (pin "1") (pinfunction "1_1") (pintype "passive"))
    )
    (net (code "111") (name "unconnected-(JP23-Pad2)") (class "Default")
      (node (ref "JP23") (pin "2") (pinfunction "2_2") (pintype "passive"))
    )
    (net (code "112") (name "unconnected-(JP23-Pad3)") (class "Default")
      (node (ref "JP23") (pin "3") (pinfunction "3_3") (pintype "passive"))
    )
    (net (code "113") (name "unconnected-(JP23-Pad4)") (class "Default")
      (node (ref "JP23") (pin "4") (pinfunction "4_4") (pintype "passive"))
    )
  )
)
